# Memory.net
KiCad netlist of a schematic drawn in Altium Designer
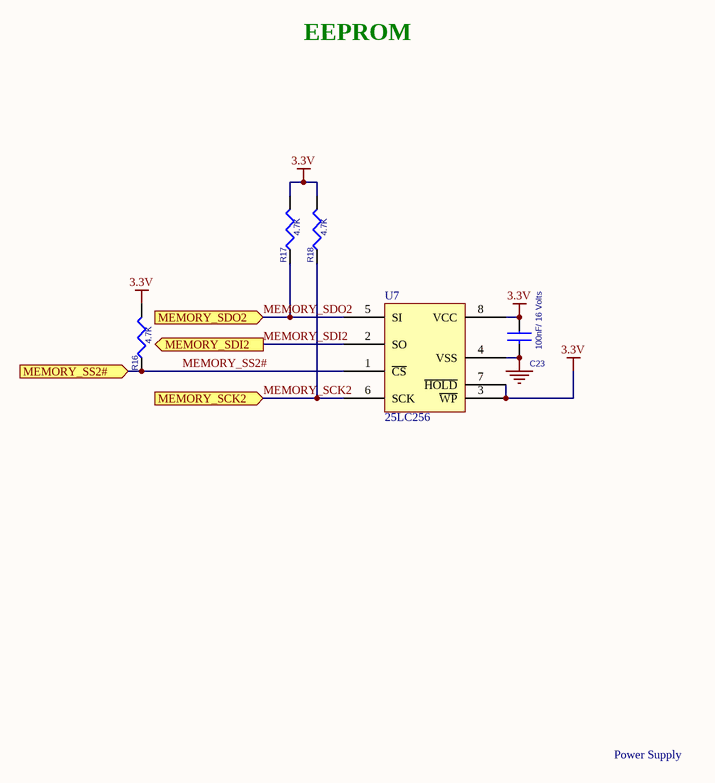
[diagram p0: Memory.SchDoc]

(export (version "E")
  (design (tool "Eeschema 10.0.6"))
  (components
    (comp (ref "C23")
      (value "100nF/ 16 Volts")
      (footprint "CAP_CERAMIC")
      (libsource (lib "combined_cart_schematic_lib") (part "CAP NP"))
    )
    (comp (ref "R16")
      (value "4.7K")
      (footprint "RES_SMD")
      (libsource (lib "combined_cart_schematic_lib") (part "RESISTOR"))
    )
    (comp (ref "R17")
      (value "4.7K")
      (footprint "RES_SMD")
      (libsource (lib "combined_cart_schematic_lib") (part "RESISTOR"))
    )
    (comp (ref "R18")
      (value "4.7K")
      (footprint "RES_SMD")
      (libsource (lib "combined_cart_schematic_lib") (part "RESISTOR"))
    )
    (comp (ref "U7")
      (value "25LC256")
      (footprint "25LC256")
      (libsource (lib "combined_cart_schematic_lib") (part "25LC256"))
    )
  )
  (nets
    (net (code "1") (name "/MEMORY_SCK2") (class "Default")
      (node (ref "R18") (pin "1") (pinfunction "1_1") (pintype "passive"))
      (node (ref "U7") (pin "6") (pinfunction "SCK_6") (pintype "passive"))
    )
    (net (code "2") (name "/MEMORY_SDI2") (class "Default")
      (node (ref "U7") (pin "2") (pinfunction "SO_2") (pintype "passive"))
    )
    (net (code "3") (name "/MEMORY_SDO2") (class "Default")
      (node (ref "R17") (pin "1") (pinfunction "1_1") (pintype "passive"))
      (node (ref "U7") (pin "5") (pinfunction "SI_5") (pintype "passive"))
    )
    (net (code "4") (name "/MEMORY_SS2#") (class "Default")
      (node (ref "R16") (pin "1") (pinfunction "1_1") (pintype "passive"))
      (node (ref "U7") (pin "1") (pinfunction "~{CS}_1") (pintype "passive"))
    )
    (net (code "5") (name "3.3V") (class "Default")
      (node (ref "C23") (pin "1") (pinfunction "1_1") (pintype "passive"))
      (node (ref "R16") (pin "2") (pinfunction "2_2") (pintype "passive"))
      (node (ref "R17") (pin "2") (pinfunction "2_2") (pintype "passive"))
      (node (ref "R18") (pin "2") (pinfunction "2_2") (pintype "passive"))
      (node (ref "U7") (pin "3") (pinfunction "~{WP}_3") (pintype "passive"))
      (node (ref "U7") (pin "7") (pinfunction "~{HOLD}_7") (pintype "passive"))
      (node (ref "U7") (pin "8") (pinfunction "VCC_8") (pintype "passive"))
    )
    (net (code "6") (name "GND_POWER") (class "Default")
      (node (ref "C23") (pin "2") (pinfunction "2_2") (pintype "passive"))
      (node (ref "U7") (pin "4") (pinfunction "VSS_4") (pintype "passive"))
    )
  )
)
